# Power.net
KiCad netlist of a schematic drawn in Altium Designer
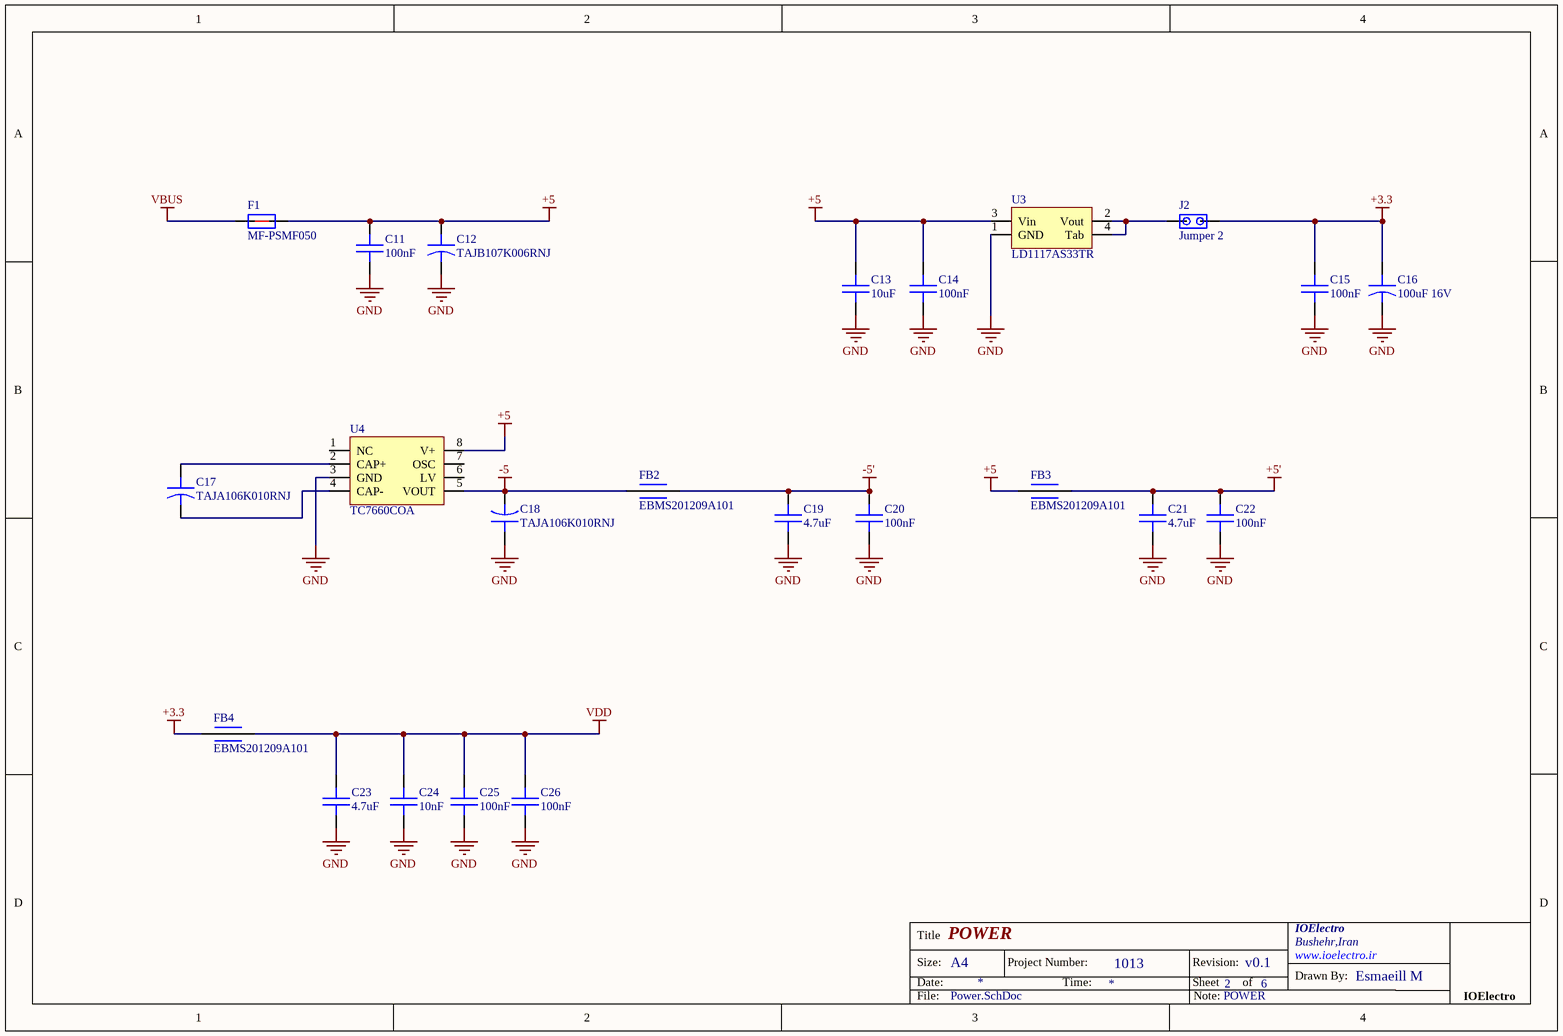
[diagram p0: Power.SchDoc]

(export (version "E")
  (design (tool "Eeschema 10.0.6"))
  (components
    (comp (ref "C11")
      (value "100nF")
      (footprint "C-0805")
      (description "SMD 0805")
      (libsource (lib "IOElectro") (part "CAP"))
    )
    (comp (ref "C12")
      (value "TAJB107K006RNJ")
      (footprint "TAJB")
      (fields
        (field (name "MANUFACTURER") "Kyocera AVX")
        (field (name "TOLERANCE") "10%")
        (field (name "VOLTAGE") "6.3V")
      )
      (libsource (lib "IOElectro") (part "TAJB107K006RNJ"))
    )
    (comp (ref "C13")
      (value "10uF")
      (footprint "C-0805")
      (description "SMD 0805")
      (libsource (lib "IOElectro") (part "CAP"))
    )
    (comp (ref "C14")
      (value "100nF")
      (footprint "C-0805")
      (description "SMD 0805")
      (libsource (lib "IOElectro") (part "CAP"))
    )
    (comp (ref "C15")
      (value "100nF")
      (footprint "C-0805")
      (description "SMD 0805")
      (libsource (lib "IOElectro") (part "CAP"))
    )
    (comp (ref "C16")
      (value "100uF 16V")
      (footprint "C-EL_6.5x7x2.5mm")
      (description "CAPACITOR ELECTROLYTIC 6.3x7mm")
      (libsource (lib "IOElectro") (part "CAP-EL"))
    )
    (comp (ref "C17")
      (value "TAJA106K010RNJ")
      (footprint "TAJA")
      (description "Capacitor;  Tantalum;  Cap 10 uF;  Tol 10%;  Vol-Rtg 10 VDC;  SMT;  3216;  ESR 3 Ohms;  TR")
      (fields (field (name "MANUFACTURER") "Kyocera AVX") (field (name "TOLERANCE") "10%"))
      (libsource (lib "IOElectro") (part "TAJA106K010RNJ"))
    )
    (comp (ref "C18")
      (value "TAJA106K010RNJ")
      (footprint "TAJA")
      (description "Capacitor;  Tantalum;  Cap 10 uF;  Tol 10%;  Vol-Rtg 10 VDC;  SMT;  3216;  ESR 3 Ohms;  TR")
      (fields (field (name "MANUFACTURER") "Kyocera AVX") (field (name "TOLERANCE") "10%"))
      (libsource (lib "IOElectro") (part "TAJA106K010RNJ"))
    )
    (comp (ref "C19")
      (value "4.7uF")
      (footprint "C-0805")
      (description "SMD 0805")
      (libsource (lib "IOElectro") (part "CAP"))
    )
    (comp (ref "C20")
      (value "100nF")
      (footprint "C-BP-Ceramic-DIP")
      (description "Ceramic Disk Capacitor 50V")
      (libsource (lib "IOElectro") (part "CAP"))
    )
    (comp (ref "C21")
      (value "4.7uF")
      (footprint "C-0805")
      (description "SMD 0805")
      (libsource (lib "IOElectro") (part "CAP"))
    )
    (comp (ref "C22")
      (value "100nF")
      (footprint "C-BP-Ceramic-DIP")
      (description "Ceramic Disk Capacitor 50V")
      (libsource (lib "IOElectro") (part "CAP"))
    )
    (comp (ref "C23")
      (value "4.7uF")
      (footprint "C-0805")
      (description "SMD 0805")
      (libsource (lib "IOElectro") (part "CAP"))
    )
    (comp (ref "C24")
      (value "10nF")
      (footprint "C-0805")
      (description "SMD 0805")
      (libsource (lib "IOElectro") (part "CAP"))
    )
    (comp (ref "C25")
      (value "100nF")
      (footprint "C-0805")
      (description "SMD 0805")
      (libsource (lib "IOElectro") (part "CAP"))
    )
    (comp (ref "C26")
      (value "100nF")
      (footprint "C-0805")
      (description "SMD 0805")
      (libsource (lib "IOElectro") (part "CAP"))
    )
    (comp (ref "F1")
      (value "MF-PSMF050")
      (footprint "MF-PSMF")
      (description "BOURNS   MF-PSMF050X-2   FUSE, RESETTABLE PTC, 6V, 500MA, 0805")
      (fields
        (field (name "MANUFACTURER") "Bourns")
        (field (name "MANUFACTURER PART NUMBER") "MF-PSMF050X-2")
      )
      (libsource (lib "IOElectro") (part "MF-PSMF050X-2"))
    )
    (comp (ref "FB2")
      (value "EBMS201209A101")
      (footprint "L-0805")
      (description "FERRITE BEAD 0805 100R 100Mhz")
      (libsource (lib "Schlib") (part "EBMS201209A101"))
    )
    (comp (ref "FB3")
      (value "EBMS201209A101")
      (footprint "L-0805")
      (description "FERRITE BEAD 0805 100R 100Mhz")
      (libsource (lib "Schlib") (part "EBMS201209A101"))
    )
    (comp (ref "FB4")
      (value "EBMS201209A101")
      (footprint "L-0805")
      (description "FERRITE BEAD 0805 100R 100Mhz")
      (libsource (lib "Schlib") (part "EBMS201209A101"))
    )
    (comp (ref "J2")
      (value "Jumper 2")
      (footprint "JAMPER-2-DIP_2.56mm")
      (description "2PIN DIP JAMPER 2.56mm")
      (libsource (lib "IOElectro") (part "JUMPER-2"))
    )
    (comp (ref "U3")
      (value "LD1117AS33TR")
      (footprint "SOT-223")
      (description "IC REG LINEAR 3.3V 1A SOT223")
      (fields (field (name "MANUFACTURER") "STMicroelectronics"))
      (libsource (lib "IOElectro") (part "LD1117AS33TR"))
    )
    (comp (ref "U4")
      (value "TC7660COA")
      (footprint "SOIC-8")
      (description "IC REG SWTCHD CAP INV 20MA 8SOIC")
      (fields (field (name "MANUFACTURER") "Microchip"))
      (libsource (lib "IOElectro") (part "TC7660COA"))
    )
  )
  (nets
    (net (code "1") (name "+3.3") (class "Default")
      (node (ref "C15") (pin "1") (pinfunction "1_1") (pintype "passive"))
      (node (ref "C16") (pin "A") (pinfunction "A_A") (pintype "passive"))
      (node (ref "FB4") (pin "1") (pinfunction "1_1") (pintype "passive"))
      (node (ref "J2") (pin "1") (pinfunction "1_1") (pintype "passive"))
    )
    (net (code "2") (name "+5") (class "Default")
      (node (ref "C11") (pin "1") (pinfunction "1_1") (pintype "passive"))
      (node (ref "C12") (pin "A") (pinfunction "A_A") (pintype "passive"))
      (node (ref "C13") (pin "1") (pinfunction "1_1") (pintype "passive"))
      (node (ref "C14") (pin "1") (pinfunction "1_1") (pintype "passive"))
      (node (ref "F1") (pin "2") (pinfunction "2_2") (pintype "passive"))
      (node (ref "FB3") (pin "1") (pinfunction "1_1") (pintype "passive"))
      (node (ref "U3") (pin "3") (pinfunction "Vin_3") (pintype "passive"))
      (node (ref "U4") (pin "8") (pinfunction "V+_8") (pintype "passive"))
    )
    (net (code "3") (name "+5'") (class "Default")
      (node (ref "C21") (pin "1") (pinfunction "1_1") (pintype "passive"))
      (node (ref "C22") (pin "2") (pinfunction "2_2") (pintype "passive"))
      (node (ref "FB3") (pin "2") (pinfunction "2_2") (pintype "passive"))
    )
    (net (code "4") (name "-5") (class "Default")
      (node (ref "C18") (pin "K") (pinfunction "K_K") (pintype "passive"))
      (node (ref "FB2") (pin "1") (pinfunction "1_1") (pintype "passive"))
      (node (ref "U4") (pin "5") (pinfunction "VOUT_5") (pintype "passive"))
    )
    (net (code "5") (name "-5'") (class "Default")
      (node (ref "C19") (pin "1") (pinfunction "1_1") (pintype "passive"))
      (node (ref "C20") (pin "2") (pinfunction "2_2") (pintype "passive"))
      (node (ref "FB2") (pin "2") (pinfunction "2_2") (pintype "passive"))
    )
    (net (code "6") (name "GND") (class "Default")
      (node (ref "C11") (pin "2") (pinfunction "2_2") (pintype "passive"))
      (node (ref "C12") (pin "K") (pinfunction "K_K") (pintype "passive"))
      (node (ref "C13") (pin "2") (pinfunction "2_2") (pintype "passive"))
      (node (ref "C14") (pin "2") (pinfunction "2_2") (pintype "passive"))
      (node (ref "C15") (pin "2") (pinfunction "2_2") (pintype "passive"))
      (node (ref "C16") (pin "K") (pinfunction "K_K") (pintype "passive"))
      (node (ref "C18") (pin "A") (pinfunction "A_A") (pintype "passive"))
      (node (ref "C19") (pin "2") (pinfunction "2_2") (pintype "passive"))
      (node (ref "C20") (pin "1") (pinfunction "1_1") (pintype "passive"))
      (node (ref "C21") (pin "2") (pinfunction "2_2") (pintype "passive"))
      (node (ref "C22") (pin "1") (pinfunction "1_1") (pintype "passive"))
      (node (ref "C23") (pin "2") (pinfunction "2_2") (pintype "passive"))
      (node (ref "C24") (pin "2") (pinfunction "2_2") (pintype "passive"))
      (node (ref "C25") (pin "2") (pinfunction "2_2") (pintype "passive"))
      (node (ref "C26") (pin "2") (pinfunction "2_2") (pintype "passive"))
      (node (ref "U3") (pin "1") (pinfunction "GND_1") (pintype "passive"))
      (node (ref "U4") (pin "3") (pinfunction "GND_3") (pintype "passive"))
    )
    (net (code "7") (name "Net-(U3-Tab)") (class "Default")
      (node (ref "J2") (pin "2") (pinfunction "2_2") (pintype "passive"))
      (node (ref "U3") (pin "2") (pinfunction "Vout_2") (pintype "passive"))
      (node (ref "U3") (pin "4") (pinfunction "Tab_4") (pintype "passive"))
    )
    (net (code "8") (name "Net-(U4-CAP+)") (class "Default")
      (node (ref "C17") (pin "A") (pinfunction "A_A") (pintype "passive"))
      (node (ref "U4") (pin "2") (pinfunction "CAP+_2") (pintype "passive"))
    )
    (net (code "9") (name "Net-(U4-CAP-)") (class "Default")
      (node (ref "C17") (pin "K") (pinfunction "K_K") (pintype "passive"))
      (node (ref "U4") (pin "4") (pinfunction "CAP-_4") (pintype "passive"))
    )
    (net (code "10") (name "VBUS") (class "Default")
      (node (ref "F1") (pin "1") (pinfunction "1_1") (pintype "passive"))
    )
    (net (code "11") (name "VDD") (class "Default")
      (node (ref "C23") (pin "1") (pinfunction "1_1") (pintype "passive"))
      (node (ref "C24") (pin "1") (pinfunction "1_1") (pintype "passive"))
      (node (ref "C25") (pin "1") (pinfunction "1_1") (pintype "passive"))
      (node (ref "C26") (pin "1") (pinfunction "1_1") (pintype "passive"))
      (node (ref "FB4") (pin "2") (pinfunction "2_2") (pintype "passive"))
    )
    (net (code "12") (name "unconnected-(U4-LV-Pad6)") (class "Default")
      (node (ref "U4") (pin "6") (pinfunction "LV_6") (pintype "passive"))
    )
    (net (code "13") (name "unconnected-(U4-NC-Pad1)") (class "Default")
      (node (ref "U4") (pin "1") (pinfunction "NC_1") (pintype "passive"))
    )
    (net (code "14") (name "unconnected-(U4-OSC-Pad7)") (class "Default")
      (node (ref "U4") (pin "7") (pinfunction "OSC_7") (pintype "passive"))
    )
  )
)
